# 3_ADSTM32_Peripheral.net
KiCad netlist of a schematic drawn in Altium Designer
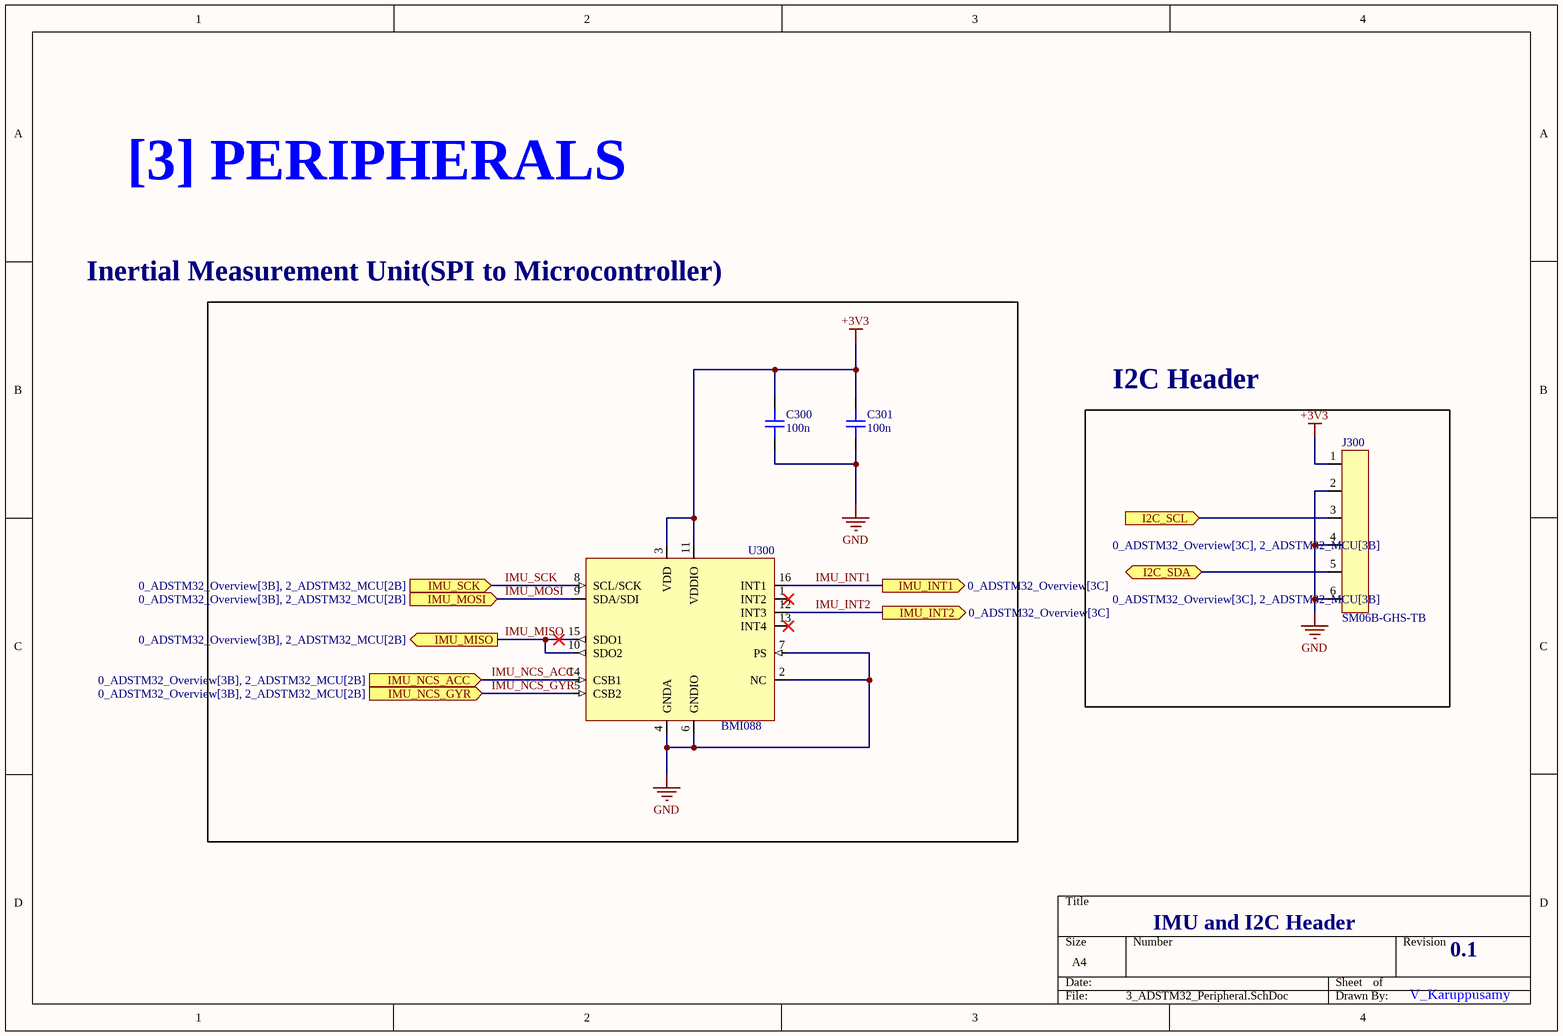
[diagram p0: 3_ADSTM32_Peripheral.SchDoc]

(export (version "E")
  (design (tool "Eeschema 10.0.6"))
  (components
    (comp (ref "C300")
      (value "100n")
      (footprint "CAP_0805")
      (description "Capacitor SMD 0805 16V")
      (libsource (lib "Schematic-Lib-PhilsLab") (part "CAP_0805_16V"))
    )
    (comp (ref "C301")
      (value "100n")
      (footprint "CAP_0805")
      (description "Capacitor SMD 0805 16V")
      (libsource (lib "Schematic-Lib-PhilsLab") (part "CAP_0805_16V"))
    )
    (comp (ref "J300")
      (value "SM06B-GHS-TB")
      (footprint "SM06B-GHS-TB")
      (description "Header Connector 6 Position 1.25MM Pitch SMD Horizontal JST GH")
      (fields (field (name "MANUFACTURER") "JST"))
      (libsource (lib "Schematic-Lib-PhilsLab") (part "SM06B-GHS-TB"))
    )
    (comp (ref "U300")
      (value "BMI088")
      (footprint "BMI088")
      (description "Inertial Measurement Unit IMU 6-Axis LGA")
      (fields (field (name "MANUFACTURER") "Bosch"))
      (libsource (lib "Schematic-Lib-PhilsLab") (part "BMI088"))
    )
  )
  (nets
    (net (code "1") (name "+3V3") (class "Default")
      (node (ref "C300") (pin "2") (pinfunction "2_2") (pintype "passive"))
      (node (ref "C301") (pin "2") (pinfunction "2_2") (pintype "passive"))
      (node (ref "J300") (pin "1") (pinfunction "1_1") (pintype "passive"))
      (node (ref "U300") (pin "11") (pinfunction "VDDIO_11") (pintype "power_in"))
      (node (ref "U300") (pin "3") (pinfunction "VDD_3") (pintype "power_in"))
    )
    (net (code "2") (name "/I2C_SCL") (class "Default")
      (node (ref "J300") (pin "3") (pinfunction "3_3") (pintype "passive"))
    )
    (net (code "3") (name "/I2C_SDA") (class "Default")
      (node (ref "J300") (pin "5") (pinfunction "5_5") (pintype "passive"))
    )
    (net (code "4") (name "/IMU_INT1") (class "Default")
      (node (ref "U300") (pin "16") (pinfunction "INT1_16") (pintype "bidirectional"))
    )
    (net (code "5") (name "/IMU_INT2") (class "Default")
      (node (ref "U300") (pin "12") (pinfunction "INT3_12") (pintype "bidirectional"))
    )
    (net (code "6") (name "/IMU_MISO") (class "Default")
      (node (ref "U300") (pin "10") (pinfunction "SDO2_10") (pintype "output"))
      (node (ref "U300") (pin "15") (pinfunction "SDO1_15") (pintype "output"))
    )
    (net (code "7") (name "/IMU_MOSI") (class "Default")
      (node (ref "U300") (pin "9") (pinfunction "SDA/SDI_9") (pintype "bidirectional"))
    )
    (net (code "8") (name "/IMU_NCS_ACC") (class "Default")
      (node (ref "U300") (pin "14") (pinfunction "CSB1_14") (pintype "input"))
    )
    (net (code "9") (name "/IMU_NCS_GYR") (class "Default")
      (node (ref "U300") (pin "5") (pinfunction "CSB2_5") (pintype "input"))
    )
    (net (code "10") (name "/IMU_SCK") (class "Default")
      (node (ref "U300") (pin "8") (pinfunction "SCL/SCK_8") (pintype "input"))
    )
    (net (code "11") (name "GND") (class "Default")
      (node (ref "C300") (pin "1") (pinfunction "1_1") (pintype "passive"))
      (node (ref "C301") (pin "1") (pinfunction "1_1") (pintype "passive"))
      (node (ref "J300") (pin "2") (pinfunction "2_2") (pintype "passive"))
      (node (ref "J300") (pin "4") (pinfunction "4_4") (pintype "passive"))
      (node (ref "J300") (pin "6") (pinfunction "6_6") (pintype "passive"))
      (node (ref "U300") (pin "2") (pinfunction "NC_2") (pintype "passive"))
      (node (ref "U300") (pin "4") (pinfunction "GNDA_4") (pintype "power_in"))
      (node (ref "U300") (pin "6") (pinfunction "GNDIO_6") (pintype "power_in"))
      (node (ref "U300") (pin "7") (pinfunction "PS_7") (pintype "input"))
    )
    (net (code "12") (name "unconnected-(U300-INT2-Pad1)") (class "Default")
      (node (ref "U300") (pin "1") (pinfunction "INT2_1") (pintype "bidirectional+no_connect"))
    )
    (net (code "13") (name "unconnected-(U300-INT4-Pad13)") (class "Default")
      (node (ref "U300") (pin "13") (pinfunction "INT4_13") (pintype "bidirectional+no_connect"))
    )
  )
)
